# SensorStick_IMUedits_HeaderPins_jesus.net
KiCad netlist of a schematic drawn in EAGLE
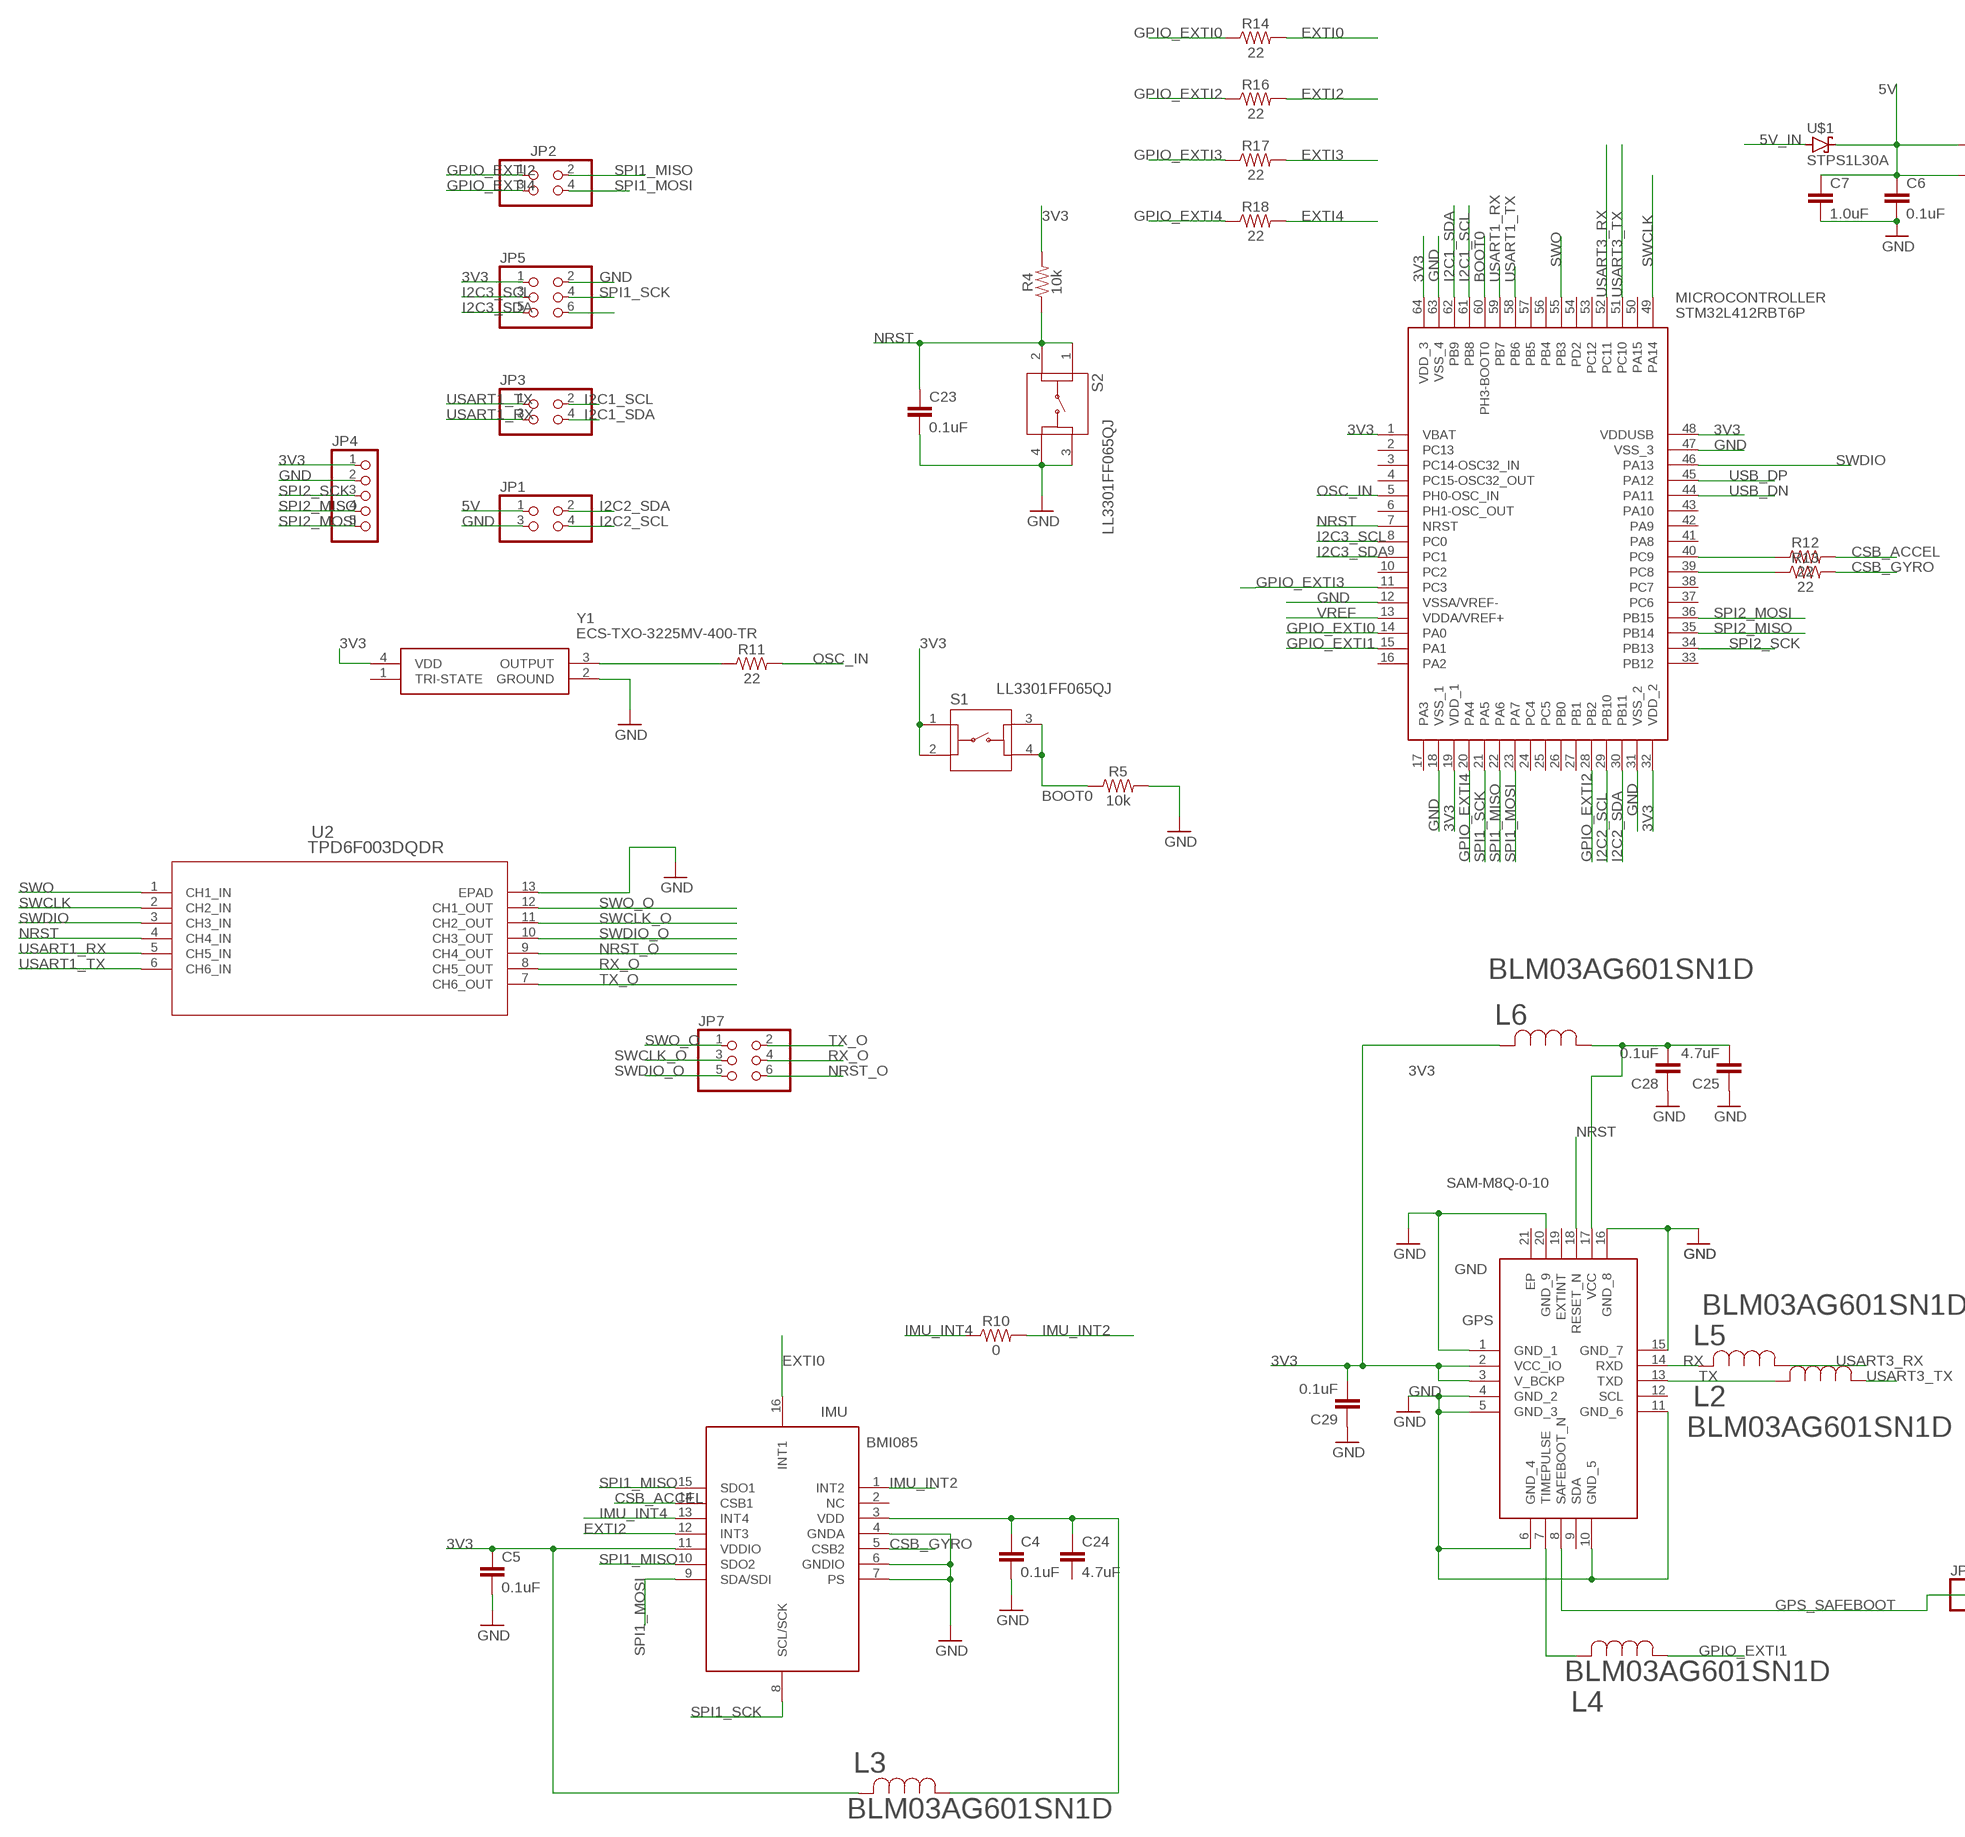
[diagram p0: schematic, sheet 1, part 1 of 2]
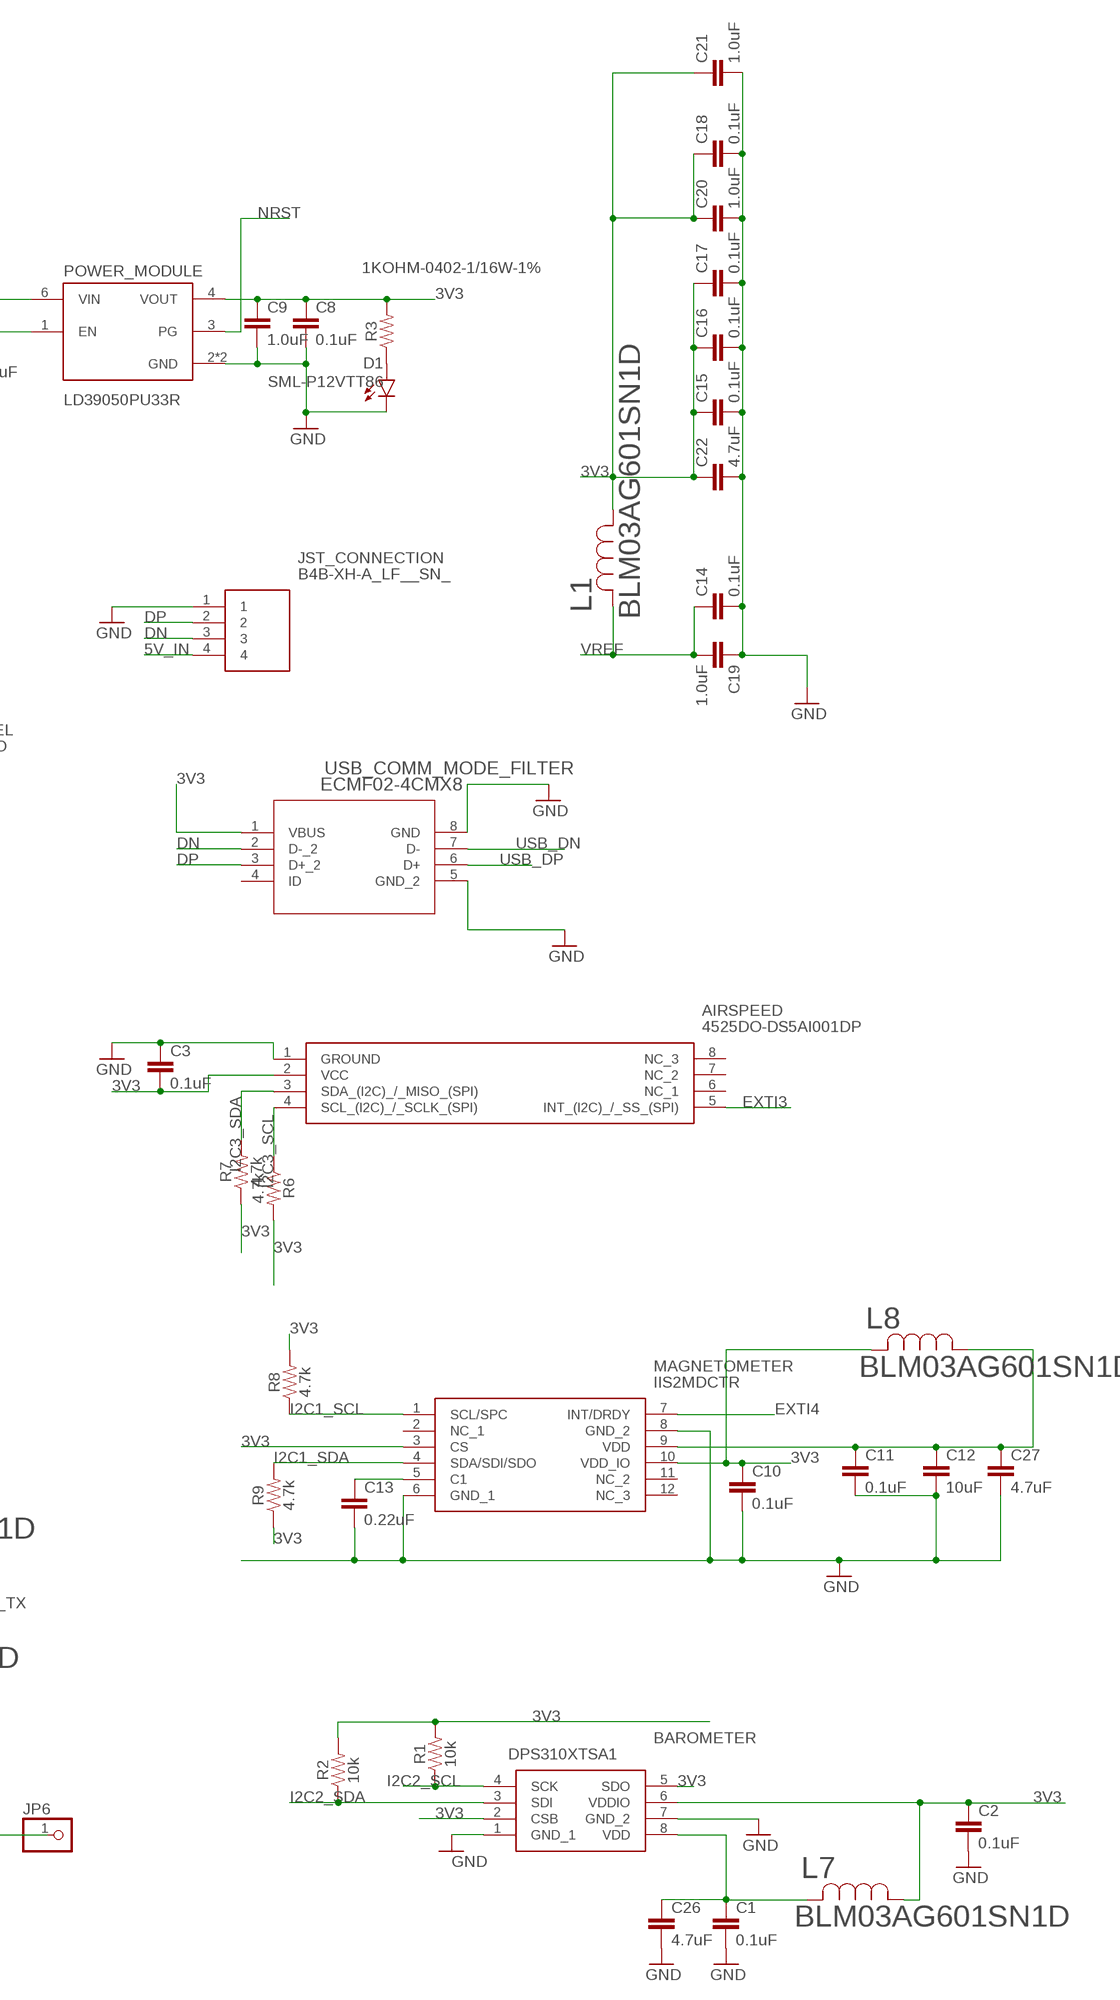
[diagram p1: schematic, sheet 1, part 2 of 2]

(export (version "E")
  (design (tool "Eeschema 10.0.6"))
  (components
    (comp (ref "AIRSPEED")
      (value "4525DO-DS5AI001DP")
      (footprint "eagle-import:4525DO-DS...P")
      (fields (field (name "MOUSER_PART_NUMBER") "824-4525DODS5AI001DP"))
      (libsource (lib "eagle-import") (part "4525DO-DS5AI001DP"))
    )
    (comp (ref "BAROMETER")
      (value "DPS310XTSA1")
      (footprint "eagle-import:DPS310XTSA1")
      (fields (field (name "MOUSER_PART_NUMBER") "726-DPS310XTSA1"))
      (libsource (lib "eagle-import") (part "DPS310XTSA1"))
    )
    (comp (ref "C1")
      (value "0.1uF")
      (footprint "eagle-import:0402")
      (libsource (lib "eagle-import") (part "0.1UF-0402-6.3V-10%-X7R"))
    )
    (comp (ref "C2")
      (value "0.1uF")
      (footprint "eagle-import:0402")
      (libsource (lib "eagle-import") (part "0.1UF-0402-6.3V-10%-X7R"))
    )
    (comp (ref "C3")
      (value "0.1uF")
      (footprint "eagle-import:0402")
      (fields (field (name "SPICEPREFIX") "C"))
      (libsource (lib "eagle-import") (part "0.1UF-0402-6.3V-10%-X7R"))
    )
    (comp (ref "C4")
      (value "0.1uF")
      (footprint "eagle-import:0402")
      (libsource (lib "eagle-import") (part "0.1UF-0402-6.3V-10%-X7R"))
    )
    (comp (ref "C5")
      (value "0.1uF")
      (footprint "eagle-import:0402")
      (libsource (lib "eagle-import") (part "0.1UF-0402-6.3V-10%-X7R"))
    )
    (comp (ref "C6")
      (value "0.1uF")
      (footprint "eagle-import:0402")
      (libsource (lib "eagle-import") (part "0.1UF-0402-6.3V-10%-X7R"))
    )
    (comp (ref "C7")
      (value "1.0uF")
      (footprint "eagle-import:0402")
      (libsource (lib "eagle-import") (part "1.0UF-0402-16V-10%"))
    )
    (comp (ref "C8")
      (value "0.1uF")
      (footprint "eagle-import:0402")
      (libsource (lib "eagle-import") (part "0.1UF-0402-6.3V-10%-X7R"))
    )
    (comp (ref "C9")
      (value "1.0uF")
      (footprint "eagle-import:0402")
      (libsource (lib "eagle-import") (part "1.0UF-0402-16V-10%"))
    )
    (comp (ref "C10")
      (value "0.1uF")
      (footprint "eagle-import:0402")
      (libsource (lib "eagle-import") (part "0.1UF-0402-6.3V-10%-X7R"))
    )
    (comp (ref "C11")
      (value "0.1uF")
      (footprint "eagle-import:0402")
      (libsource (lib "eagle-import") (part "0.1UF-0402-6.3V-10%-X7R"))
    )
    (comp (ref "C12")
      (value "10uF")
      (footprint "eagle-import:0603")
      (libsource (lib "eagle-import") (part "10UF-0603-6.3V-20%"))
    )
    (comp (ref "C13")
      (value "0.22uF")
      (footprint "eagle-import:0603")
      (libsource (lib "eagle-import") (part "0.22UF-0603-25V-10%"))
    )
    (comp (ref "C14")
      (value "0.1uF")
      (footprint "eagle-import:0603")
      (libsource (lib "eagle-import") (part "SparkFun-Capacitors_510_0.1UF-0603-25V-5%"))
    )
    (comp (ref "C15")
      (value "0.1uF")
      (footprint "eagle-import:0603")
      (libsource (lib "eagle-import") (part "SparkFun-Capacitors_510_0.1UF-0603-25V-5%"))
    )
    (comp (ref "C16")
      (value "0.1uF")
      (footprint "eagle-import:0603")
      (libsource (lib "eagle-import") (part "SparkFun-Capacitors_510_0.1UF-0603-25V-5%"))
    )
    (comp (ref "C17")
      (value "0.1uF")
      (footprint "eagle-import:0603")
      (libsource (lib "eagle-import") (part "SparkFun-Capacitors_510_0.1UF-0603-25V-5%"))
    )
    (comp (ref "C18")
      (value "0.1uF")
      (footprint "eagle-import:0603")
      (libsource (lib "eagle-import") (part "SparkFun-Capacitors_510_0.1UF-0603-25V-5%"))
    )
    (comp (ref "C19")
      (value "1.0uF")
      (footprint "eagle-import:0805")
      (libsource (lib "eagle-import") (part "SparkFun-Capacitors_510_1.0UF-0805-25V-10%"))
    )
    (comp (ref "C20")
      (value "1.0uF")
      (footprint "eagle-import:0805")
      (libsource (lib "eagle-import") (part "SparkFun-Capacitors_510_1.0UF-0805-25V-10%"))
    )
    (comp (ref "C21")
      (value "1.0uF")
      (footprint "eagle-import:0805")
      (libsource (lib "eagle-import") (part "SparkFun-Capacitors_510_1.0UF-0805-25V-10%"))
    )
    (comp (ref "C22")
      (value "4.7uF")
      (footprint "eagle-import:0603")
      (libsource (lib "eagle-import") (part "4.7UF0603"))
    )
    (comp (ref "C23")
      (value "0.1uF")
      (footprint "eagle-import:0603")
      (libsource (lib "eagle-import") (part "SparkFun-Capacitors_510_0.1UF-0603-25V-5%"))
    )
    (comp (ref "C24")
      (value "4.7uF")
      (footprint "eagle-import:0603")
      (libsource (lib "eagle-import") (part "4.7UF0603"))
    )
    (comp (ref "C25")
      (value "4.7uF")
      (footprint "eagle-import:0603")
      (libsource (lib "eagle-import") (part "4.7UF0603"))
    )
    (comp (ref "C26")
      (value "4.7uF")
      (footprint "eagle-import:0603")
      (libsource (lib "eagle-import") (part "4.7UF0603"))
    )
    (comp (ref "C27")
      (value "4.7uF")
      (footprint "eagle-import:0603")
      (libsource (lib "eagle-import") (part "4.7UF0603"))
    )
    (comp (ref "C28")
      (value "0.1uF")
      (footprint "eagle-import:0402")
      (libsource (lib "eagle-import") (part "SparkFun-Capacitors_510_0.1UF-0402-16V-10%"))
    )
    (comp (ref "C29")
      (value "0.1uF")
      (footprint "eagle-import:0402")
      (libsource (lib "eagle-import") (part "SparkFun-Capacitors_510_0.1UF-0402-16V-10%"))
    )
    (comp (ref "D1")
      (value "SML-P12VTT86")
      (footprint "eagle-import:LED_SML-P11UTT86R")
      (fields (field (name "MF") "Rohm"))
      (libsource (lib "eagle-import") (part "SML-P12VTT86"))
    )
    (comp (ref "GPS")
      (value "SAM-M8Q-0-10")
      (footprint "eagle-import:SAMM8Q010")
      (libsource (lib "eagle-import") (part "SAM-M8Q-0-10"))
    )
    (comp (ref "IMU")
      (value "BMI085")
      (footprint "eagle-import:BMI085")
      (fields (field (name "MOUSER_PART_NUMBER") "262-BMI085"))
      (libsource (lib "eagle-import") (part "BMI085"))
    )
    (comp (ref "JP1")
      (value "PINHD-2X2")
      (footprint "eagle-import:2X02")
      (libsource (lib "eagle-import") (part "PINHD-2X2"))
    )
    (comp (ref "JP2")
      (value "PINHD-2X2")
      (footprint "eagle-import:2X02")
      (libsource (lib "eagle-import") (part "PINHD-2X2"))
    )
    (comp (ref "JP3")
      (value "PINHD-2X2")
      (footprint "eagle-import:2X02")
      (libsource (lib "eagle-import") (part "PINHD-2X2"))
    )
    (comp (ref "JP4")
      (value "PINHD-1X5")
      (footprint "eagle-import:1X05")
      (libsource (lib "eagle-import") (part "PINHD-1X5"))
    )
    (comp (ref "JP5")
      (value "PINHD-2X3")
      (footprint "eagle-import:2X03")
      (libsource (lib "eagle-import") (part "PINHD-2X3"))
    )
    (comp (ref "JP6")
      (value "PINHD-1X1")
      (footprint "eagle-import:1X01")
      (libsource (lib "eagle-import") (part "PINHD-1X1"))
    )
    (comp (ref "JP7")
      (value "PINHD-2X3")
      (footprint "eagle-import:2X03")
      (libsource (lib "eagle-import") (part "PINHD-2X3"))
    )
    (comp (ref "JST_CONNECTION")
      (value "B4B-XH-A_LF__SN_")
      (footprint "eagle-import:B4BXHALFSN")
      (fields (field (name "ARROW_PART_NUMBER") "B4B-XH-A(LF)(SN)"))
      (libsource (lib "eagle-import") (part "B4B-XH-A_LF__SN_"))
    )
    (comp (ref "L1")
      (value "BLM03AG601SN1D")
      (footprint "eagle-import:IND_BLM03_0201_MUR")
      (fields (field (name "COPYRIGHT") "Copyright (C) 2023 Ultra Librarian. All rights reserved."))
      (libsource (lib "eagle-import") (part "BLM03AG601SN1D"))
    )
    (comp (ref "L2")
      (value "BLM03AG601SN1D")
      (footprint "eagle-import:IND_BLM03_0201_MUR")
      (fields (field (name "COPYRIGHT") "Copyright (C) 2023 Ultra Librarian. All rights reserved."))
      (libsource (lib "eagle-import") (part "BLM03AG601SN1D"))
    )
    (comp (ref "L3")
      (value "BLM03AG601SN1D")
      (footprint "eagle-import:IND_BLM03_0201_MUR")
      (fields (field (name "COPYRIGHT") "Copyright (C) 2023 Ultra Librarian. All rights reserved."))
      (libsource (lib "eagle-import") (part "BLM03AG601SN1D"))
    )
    (comp (ref "L4")
      (value "BLM03AG601SN1D")
      (footprint "eagle-import:IND_BLM03_0201_MUR")
      (fields (field (name "COPYRIGHT") "Copyright (C) 2023 Ultra Librarian. All rights reserved."))
      (libsource (lib "eagle-import") (part "BLM03AG601SN1D"))
    )
    (comp (ref "L5")
      (value "BLM03AG601SN1D")
      (footprint "eagle-import:IND_BLM03_0201_MUR")
      (fields (field (name "COPYRIGHT") "Copyright (C) 2023 Ultra Librarian. All rights reserved."))
      (libsource (lib "eagle-import") (part "BLM03AG601SN1D"))
    )
    (comp (ref "L6")
      (value "BLM03AG601SN1D")
      (footprint "eagle-import:IND_BLM03_0201_MUR")
      (fields (field (name "COPYRIGHT") "Copyright (C) 2023 Ultra Librarian. All rights reserved."))
      (libsource (lib "eagle-import") (part "BLM03AG601SN1D"))
    )
    (comp (ref "L7")
      (value "BLM03AG601SN1D")
      (footprint "eagle-import:IND_BLM03_0201_MUR")
      (fields (field (name "COPYRIGHT") "Copyright (C) 2023 Ultra Librarian. All rights reserved."))
      (libsource (lib "eagle-import") (part "BLM03AG601SN1D"))
    )
    (comp (ref "L8")
      (value "BLM03AG601SN1D")
      (footprint "eagle-import:IND_BLM03_0201_MUR")
      (fields (field (name "COPYRIGHT") "Copyright (C) 2023 Ultra Librarian. All rights reserved."))
      (libsource (lib "eagle-import") (part "BLM03AG601SN1D"))
    )
    (comp (ref "MAGNETOMETER")
      (value "IIS2MDCTR")
      (footprint "eagle-import:IIS2MDCTR")
      (fields (field (name "MOUSER_PART_NUMBER") "511-IIS2MDCTR"))
      (libsource (lib "eagle-import") (part "IIS2MDCTR"))
    )
    (comp (ref "MICROCONTROLLER")
      (value "STM32L412RBT6P")
      (footprint "eagle-import:QFP50P1200X1200X160-64N")
      (fields (field (name "MOUSER_PART_NUMBER") "511-STM32L412RBT6P"))
      (libsource (lib "eagle-import") (part "STM32L412RBT6P"))
    )
    (comp (ref "POWER_MODULE")
      (value "LD39050PU33R")
      (footprint "eagle-import:SON95P300X300X100-7N")
      (fields (field (name "MF") "STMicroelectronics"))
      (libsource (lib "eagle-import") (part "LD39050PU33R"))
    )
    (comp (ref "R1")
      (value "10k")
      (footprint "eagle-import:0402")
      (libsource (lib "eagle-import") (part "10KOHM-0402-1/16W-1%"))
    )
    (comp (ref "R2")
      (value "10k")
      (footprint "eagle-import:0402")
      (libsource (lib "eagle-import") (part "10KOHM-0402-1/16W-1%"))
    )
    (comp (ref "R3")
      (value "1KOHM-0402-1/16W-1%")
      (footprint "eagle-import:0402")
      (libsource (lib "eagle-import") (part "1KOHM-0402-1/16W-1%"))
    )
    (comp (ref "R4")
      (value "10k")
      (footprint "eagle-import:0603")
      (libsource (lib "eagle-import") (part "SparkFun-Resistors_532_10KOHM-0603-1/10W-1%"))
    )
    (comp (ref "R5")
      (value "10k")
      (footprint "eagle-import:0603")
      (libsource (lib "eagle-import") (part "SparkFun-Resistors_532_10KOHM-0603-1/10W-1%"))
    )
    (comp (ref "R6")
      (value "4.7k")
      (footprint "eagle-import:0603")
      (libsource (lib "eagle-import") (part "4.7KOHM-0603-1/10W-1%"))
    )
    (comp (ref "R7")
      (value "4.7k")
      (footprint "eagle-import:0603")
      (libsource (lib "eagle-import") (part "4.7KOHM-0603-1/10W-1%"))
    )
    (comp (ref "R8")
      (value "4.7k")
      (footprint "eagle-import:0603")
      (libsource (lib "eagle-import") (part "4.7KOHM-0603-1/10W-1%"))
    )
    (comp (ref "R9")
      (value "4.7k")
      (footprint "eagle-import:0603")
      (libsource (lib "eagle-import") (part "4.7KOHM-0603-1/10W-1%"))
    )
    (comp (ref "R10")
      (value "0")
      (footprint "eagle-import:0603")
      (libsource (lib "eagle-import") (part "0OHM-0603-1/10W-5%"))
    )
    (comp (ref "R11")
      (value "22")
      (footprint "eagle-import:0402")
      (libsource (lib "eagle-import") (part "22OHM-0402-1/10W-1%"))
    )
    (comp (ref "R12")
      (value "22")
      (footprint "eagle-import:0402")
      (libsource (lib "eagle-import") (part "22OHM-0402-1/10W-1%"))
    )
    (comp (ref "R13")
      (value "22")
      (footprint "eagle-import:0402")
      (libsource (lib "eagle-import") (part "22OHM-0402-1/10W-1%"))
    )
    (comp (ref "R14")
      (value "22")
      (footprint "eagle-import:0402")
      (libsource (lib "eagle-import") (part "22OHM-0402-1/10W-1%"))
    )
    (comp (ref "R16")
      (value "22")
      (footprint "eagle-import:0402")
      (libsource (lib "eagle-import") (part "22OHM-0402-1/10W-1%"))
    )
    (comp (ref "R17")
      (value "22")
      (footprint "eagle-import:0402")
      (libsource (lib "eagle-import") (part "22OHM-0402-1/10W-1%"))
    )
    (comp (ref "R18")
      (value "22")
      (footprint "eagle-import:0402")
      (libsource (lib "eagle-import") (part "22OHM-0402-1/10W-1%"))
    )
    (comp (ref "S1")
      (value "LL3301FF065QJ")
      (footprint "eagle-import:LL3301FF065QJ")
      (fields (field (name "MOUSER_PART_NUMBER") "612-LL3301FF065QJ"))
      (libsource (lib "eagle-import") (part "LL3301FF065QJ"))
    )
    (comp (ref "S2")
      (value "LL3301FF065QJ")
      (footprint "eagle-import:LL3301FF065QJ")
      (fields (field (name "MOUSER_PART_NUMBER") "612-LL3301FF065QJ"))
      (libsource (lib "eagle-import") (part "LL3301FF065QJ"))
    )
    (comp (ref "U$1")
      (value "STPS1L30A")
      (footprint "eagle-import:DIOM5226X223N")
      (libsource (lib "eagle-import") (part "STPS1L30A"))
    )
    (comp (ref "U2")
      (value "TPD6F003DQDR")
      (footprint "eagle-import:DQD12_2X0P4")
      (fields (field (name "COPYRIGHT") "Copyright (C) 2023 Ultra Librarian. All rights reserved."))
      (libsource (lib "eagle-import") (part "TPD6F003DQDR"))
    )
    (comp (ref "USB_COMM_MODE_FILTER")
      (value "ECMF02-4CMX8")
      (footprint "eagle-import:MICRO_QFN-8L_STM")
      (fields (field (name "COPYRIGHT") "Copyright (C) 2023 Ultra Librarian. All rights reserved."))
      (libsource (lib "eagle-import") (part "ECMF02-4CMX8"))
    )
    (comp (ref "Y1")
      (value "ECS-TXO-3225MV-400-TR")
      (footprint "eagle-import:ECSTXO3225MV400TR")
      (libsource (lib "eagle-import") (part "ECS-TXO-3225MV-400-TR"))
    )
  )
  (nets
    (net (code "1") (name "/3V3") (class "Default")
      (node (ref "AIRSPEED") (pin "2") (pinfunction "VCC_2") (pintype "power_in"))
      (node (ref "BAROMETER") (pin "2") (pinfunction "CSB_2") (pintype "bidirectional"))
      (node (ref "BAROMETER") (pin "5") (pinfunction "SDO_5") (pintype "bidirectional"))
      (node (ref "BAROMETER") (pin "6") (pinfunction "VDDIO_6") (pintype "bidirectional"))
      (node (ref "C10") (pin "1") (pinfunction "1_1") (pintype "passive"))
      (node (ref "C15") (pin "1") (pinfunction "1_1") (pintype "passive"))
      (node (ref "C16") (pin "1") (pinfunction "1_1") (pintype "passive"))
      (node (ref "C17") (pin "1") (pinfunction "1_1") (pintype "passive"))
      (node (ref "C18") (pin "1") (pinfunction "1_1") (pintype "passive"))
      (node (ref "C2") (pin "1") (pinfunction "1_1") (pintype "passive"))
      (node (ref "C20") (pin "1") (pinfunction "1_1") (pintype "passive"))
      (node (ref "C21") (pin "1") (pinfunction "1_1") (pintype "passive"))
      (node (ref "C22") (pin "1") (pinfunction "1_1") (pintype "passive"))
      (node (ref "C29") (pin "2") (pinfunction "2_2") (pintype "passive"))
      (node (ref "C3") (pin "2") (pinfunction "2_2") (pintype "passive"))
      (node (ref "C5") (pin "1") (pinfunction "1_1") (pintype "passive"))
      (node (ref "C8") (pin "1") (pinfunction "1_1") (pintype "passive"))
      (node (ref "C9") (pin "1") (pinfunction "1_1") (pintype "passive"))
      (node (ref "GPS") (pin "2") (pinfunction "VCC_IO_2") (pintype "bidirectional"))
      (node (ref "GPS") (pin "3") (pinfunction "V_BCKP_3") (pintype "bidirectional"))
      (node (ref "IMU") (pin "11") (pinfunction "VDDIO_11") (pintype "bidirectional"))
      (node (ref "JP4") (pin "1") (pinfunction "1_1") (pintype "passive"))
      (node (ref "JP5") (pin "1") (pinfunction "1_1") (pintype "passive"))
      (node (ref "L1") (pin "1") (pinfunction "1_1") (pintype "passive"))
      (node (ref "L3") (pin "2") (pinfunction "2_2") (pintype "passive"))
      (node (ref "L6") (pin "2") (pinfunction "2_2") (pintype "passive"))
      (node (ref "L7") (pin "1") (pinfunction "1_1") (pintype "passive"))
      (node (ref "L8") (pin "2") (pinfunction "2_2") (pintype "passive"))
      (node (ref "MAGNETOMETER") (pin "10") (pinfunction "VDD_IO_10") (pintype "bidirectional"))
      (node (ref "MAGNETOMETER") (pin "3") (pinfunction "CS_3") (pintype "bidirectional"))
      (node (ref "MICROCONTROLLER") (pin "1") (pinfunction "VBAT_1") (pintype "bidirectional"))
      (node (ref "MICROCONTROLLER") (pin "19") (pinfunction "VDD_1_19") (pintype "bidirectional"))
      (node (ref "MICROCONTROLLER") (pin "32") (pinfunction "VDD_2_32") (pintype "bidirectional"))
      (node (ref "MICROCONTROLLER") (pin "48") (pinfunction "VDDUSB_48") (pintype "bidirectional"))
      (node (ref "MICROCONTROLLER") (pin "64") (pinfunction "VDD_3_64") (pintype "bidirectional"))
      (node (ref "POWER_MODULE") (pin "4") (pinfunction "VOUT_4") (pintype "output"))
      (node (ref "R1") (pin "2") (pinfunction "2_2") (pintype "passive"))
      (node (ref "R2") (pin "2") (pinfunction "2_2") (pintype "passive"))
      (node (ref "R3") (pin "2") (pinfunction "2_2") (pintype "passive"))
      (node (ref "R4") (pin "2") (pinfunction "2_2") (pintype "passive"))
      (node (ref "R6") (pin "2") (pinfunction "2_2") (pintype "passive"))
      (node (ref "R7") (pin "1") (pinfunction "1_1") (pintype "passive"))
      (node (ref "R8") (pin "2") (pinfunction "2_2") (pintype "passive"))
      (node (ref "R9") (pin "1") (pinfunction "1_1") (pintype "passive"))
      (node (ref "S1") (pin "1") (pinfunction "1_1") (pintype "passive"))
      (node (ref "S1") (pin "2") (pinfunction "2_2") (pintype "passive"))
      (node (ref "USB_COMM_MODE_FILTER") (pin "1") (pinfunction "VBUS_1") (pintype "power_in"))
      (node (ref "Y1") (pin "4") (pinfunction "VDD_4") (pintype "bidirectional"))
    )
    (net (code "2") (name "/5V") (class "Default")
      (node (ref "C6") (pin "1") (pinfunction "1_1") (pintype "passive"))
      (node (ref "C7") (pin "1") (pinfunction "1_1") (pintype "passive"))
      (node (ref "JP1") (pin "1") (pinfunction "1_1") (pintype "passive"))
      (node (ref "POWER_MODULE") (pin "1") (pinfunction "EN_1") (pintype "input"))
      (node (ref "POWER_MODULE") (pin "6") (pinfunction "VIN_6") (pintype "power_in"))
      (node (ref "U$1") (pin "1") (pinfunction "C_1") (pintype "passive"))
    )
    (net (code "3") (name "/5V_IN") (class "Default")
      (node (ref "JST_CONNECTION") (pin "4") (pinfunction "4_4") (pintype "bidirectional"))
      (node (ref "U$1") (pin "2") (pinfunction "A_2") (pintype "passive"))
    )
    (net (code "4") (name "/BOOT0") (class "Default")
      (node (ref "MICROCONTROLLER") (pin "60") (pinfunction "PH3-BOOT0_60") (pintype "bidirectional"))
      (node (ref "R5") (pin "1") (pinfunction "1_1") (pintype "passive"))
      (node (ref "S1") (pin "3") (pinfunction "3_3") (pintype "passive"))
      (node (ref "S1") (pin "4") (pinfunction "4_4") (pintype "passive"))
    )
    (net (code "5") (name "/CSB_ACCEL") (class "Default")
      (node (ref "IMU") (pin "14") (pinfunction "CSB1_14") (pintype "bidirectional"))
      (node (ref "R12") (pin "2") (pinfunction "2_2") (pintype "passive"))
    )
    (net (code "6") (name "/CSB_GYRO") (class "Default")
      (node (ref "IMU") (pin "5") (pinfunction "CSB2_5") (pintype "bidirectional"))
      (node (ref "R13") (pin "2") (pinfunction "2_2") (pintype "passive"))
    )
    (net (code "7") (name "/DN") (class "Default")
      (node (ref "JST_CONNECTION") (pin "3") (pinfunction "3_3") (pintype "bidirectional"))
      (node (ref "USB_COMM_MODE_FILTER") (pin "2") (pinfunction "D-_2_2") (pintype "bidirectional"))
    )
    (net (code "8") (name "/DP") (class "Default")
      (node (ref "JST_CONNECTION") (pin "2") (pinfunction "2_2") (pintype "bidirectional"))
      (node (ref "USB_COMM_MODE_FILTER") (pin "3") (pinfunction "D+_2_3") (pintype "bidirectional"))
    )
    (net (code "9") (name "/EXTI0") (class "Default")
      (node (ref "IMU") (pin "16") (pinfunction "INT1_16") (pintype "bidirectional"))
      (node (ref "R14") (pin "2") (pinfunction "2_2") (pintype "passive"))
    )
    (net (code "10") (name "/EXTI2") (class "Default")
      (node (ref "IMU") (pin "12") (pinfunction "INT3_12") (pintype "bidirectional"))
      (node (ref "R16") (pin "2") (pinfunction "2_2") (pintype "passive"))
    )
    (net (code "11") (name "/EXTI3") (class "Default")
      (node (ref "AIRSPEED") (pin "5") (pinfunction "INT_(I2C)_/_SS_(SPI)_5") (pintype "bidirectional"))
      (node (ref "R17") (pin "2") (pinfunction "2_2") (pintype "passive"))
    )
    (net (code "12") (name "/EXTI4") (class "Default")
      (node (ref "MAGNETOMETER") (pin "7") (pinfunction "INT/DRDY_7") (pintype "bidirectional"))
      (node (ref "R18") (pin "2") (pinfunction "2_2") (pintype "passive"))
    )
    (net (code "13") (name "/GPIO_EXTI0") (class "Default")
      (node (ref "MICROCONTROLLER") (pin "14") (pinfunction "PA0_14") (pintype "bidirectional"))
      (node (ref "R14") (pin "1") (pinfunction "1_1") (pintype "passive"))
    )
    (net (code "14") (name "/GPIO_EXTI1") (class "Default")
      (node (ref "L4") (pin "1") (pinfunction "1_1") (pintype "passive"))
      (node (ref "MICROCONTROLLER") (pin "15") (pinfunction "PA1_15") (pintype "bidirectional"))
    )
    (net (code "15") (name "/GPIO_EXTI2") (class "Default")
      (node (ref "JP2") (pin "1") (pinfunction "1_1") (pintype "passive"))
      (node (ref "MICROCONTROLLER") (pin "28") (pinfunction "PB2_28") (pintype "bidirectional"))
      (node (ref "R16") (pin "1") (pinfunction "1_1") (pintype "passive"))
    )
    (net (code "16") (name "/GPIO_EXTI3") (class "Default")
      (node (ref "MICROCONTROLLER") (pin "11") (pinfunction "PC3_11") (pintype "bidirectional"))
      (node (ref "R17") (pin "1") (pinfunction "1_1") (pintype "passive"))
    )
    (net (code "17") (name "/GPIO_EXTI4") (class "Default")
      (node (ref "JP2") (pin "3") (pinfunction "3_3") (pintype "passive"))
      (node (ref "MICROCONTROLLER") (pin "20") (pinfunction "PA4_20") (pintype "bidirectional"))
      (node (ref "R18") (pin "1") (pinfunction "1_1") (pintype "passive"))
    )
    (net (code "18") (name "/GPS_SAFEBOOT") (class "Default")
      (node (ref "GPS") (pin "8") (pinfunction "SAFEBOOT_N_8") (pintype "bidirectional"))
      (node (ref "JP6") (pin "1") (pinfunction "1_1") (pintype "passive"))
    )
    (net (code "19") (name "/I2C1_SCL") (class "Default")
      (node (ref "JP3") (pin "2") (pinfunction "2_2") (pintype "passive"))
      (node (ref "MAGNETOMETER") (pin "1") (pinfunction "SCL/SPC_1") (pintype "bidirectional"))
      (node (ref "MICROCONTROLLER") (pin "61") (pinfunction "PB8_61") (pintype "bidirectional"))
      (node (ref "R8") (pin "1") (pinfunction "1_1") (pintype "passive"))
    )
    (net (code "20") (name "/I2C1_SDA") (class "Default")
      (node (ref "JP3") (pin "4") (pinfunction "4_4") (pintype "passive"))
      (node (ref "MAGNETOMETER") (pin "4") (pinfunction "SDA/SDI/SDO_4") (pintype "bidirectional"))
      (node (ref "MICROCONTROLLER") (pin "62") (pinfunction "PB9_62") (pintype "bidirectional"))
      (node (ref "R9") (pin "2") (pinfunction "2_2") (pintype "passive"))
    )
    (net (code "21") (name "/I2C2_SCL") (class "Default")
      (node (ref "BAROMETER") (pin "4") (pinfunction "SCK_4") (pintype "bidirectional"))
      (node (ref "JP1") (pin "4") (pinfunction "4_4") (pintype "passive"))
      (node (ref "MICROCONTROLLER") (pin "29") (pinfunction "PB10_29") (pintype "bidirectional"))
      (node (ref "R1") (pin "1") (pinfunction "1_1") (pintype "passive"))
    )
    (net (code "22") (name "/I2C2_SDA") (class "Default")
      (node (ref "BAROMETER") (pin "3") (pinfunction "SDI_3") (pintype "bidirectional"))
      (node (ref "JP1") (pin "2") (pinfunction "2_2") (pintype "passive"))
      (node (ref "MICROCONTROLLER") (pin "30") (pinfunction "PB11_30") (pintype "bidirectional"))
      (node (ref "R2") (pin "1") (pinfunction "1_1") (pintype "passive"))
    )
    (net (code "23") (name "/I2C3_SCL") (class "Default")
      (node (ref "AIRSPEED") (pin "4") (pinfunction "SCL_(I2C)_/_SCLK_(SPI)_4") (pintype "bidirectional"))
      (node (ref "JP5") (pin "3") (pinfunction "3_3") (pintype "passive"))
      (node (ref "MICROCONTROLLER") (pin "8") (pinfunction "PC0_8") (pintype "bidirectional"))
      (node (ref "R6") (pin "1") (pinfunction "1_1") (pintype "passive"))
    )
    (net (code "24") (name "/I2C3_SDA") (class "Default")
      (node (ref "AIRSPEED") (pin "3") (pinfunction "SDA_(I2C)_/_MISO_(SPI)_3") (pintype "bidirectional"))
      (node (ref "JP5") (pin "5") (pinfunction "5_5") (pintype "passive"))
      (node (ref "MICROCONTROLLER") (pin "9") (pinfunction "PC1_9") (pintype "bidirectional"))
      (node (ref "R7") (pin "2") (pinfunction "2_2") (pintype "passive"))
    )
    (net (code "25") (name "/IMU_INT2") (class "Default")
      (node (ref "IMU") (pin "1") (pinfunction "INT2_1") (pintype "bidirectional"))
      (node (ref "R10") (pin "2") (pinfunction "2_2") (pintype "passive"))
    )
    (net (code "26") (name "/IMU_INT4") (class "Default")
      (node (ref "IMU") (pin "13") (pinfunction "INT4_13") (pintype "bidirectional"))
      (node (ref "R10") (pin "1") (pinfunction "1_1") (pintype "passive"))
    )
    (net (code "27") (name "/NRST") (class "Default")
      (node (ref "C23") (pin "1") (pinfunction "1_1") (pintype "passive"))
      (node (ref "GPS") (pin "18") (pinfunction "RESET_N_18") (pintype "bidirectional"))
      (node (ref "MICROCONTROLLER") (pin "7") (pinfunction "NRST_7") (pintype "bidirectional"))
      (node (ref "POWER_MODULE") (pin "3") (pinfunction "PG_3") (pintype "bidirectional"))
      (node (ref "R4") (pin "1") (pinfunction "1_1") (pintype "passive"))
      (node (ref "S2") (pin "1") (pinfunction "1_1") (pintype "passive"))
      (node (ref "S2") (pin "2") (pinfunction "2_2") (pintype "passive"))
      (node (ref "U2") (pin "4") (pinfunction "CH4_IN_4") (pintype "input"))
    )
    (net (code "28") (name "/NRST_O") (class "Default")
      (node (ref "JP7") (pin "6") (pinfunction "6_6") (pintype "passive"))
      (node (ref "U2") (pin "9") (pinfunction "CH4_OUT_9") (pintype "output"))
    )
    (net (code "29") (name "/OSC_IN") (class "Default")
      (node (ref "MICROCONTROLLER") (pin "5") (pinfunction "PH0-OSC_IN_5") (pintype "bidirectional"))
      (node (ref "R11") (pin "2") (pinfunction "2_2") (pintype "passive"))
    )
    (net (code "30") (name "/RX") (class "Default")
      (node (ref "GPS") (pin "14") (pinfunction "RXD_14") (pintype "bidirectional"))
      (node (ref "L5") (pin "2") (pinfunction "2_2") (pintype "passive"))
    )
    (net (code "31") (name "/RX_O") (class "Default")
      (node (ref "JP7") (pin "4") (pinfunction "4_4") (pintype "passive"))
      (node (ref "U2") (pin "8") (pinfunction "CH5_OUT_8") (pintype "output"))
    )
    (net (code "32") (name "/SPI1_MISO") (class "Default")
      (node (ref "IMU") (pin "10") (pinfunction "SDO2_10") (pintype "bidirectional"))
      (node (ref "IMU") (pin "15") (pinfunction "SDO1_15") (pintype "bidirectional"))
      (node (ref "JP2") (pin "2") (pinfunction "2_2") (pintype "passive"))
      (node (ref "MICROCONTROLLER") (pin "22") (pinfunction "PA6_22") (pintype "bidirectional"))
    )
    (net (code "33") (name "/SPI1_MOSI") (class "Default")
      (node (ref "IMU") (pin "9") (pinfunction "SDA/SDI_9") (pintype "bidirectional"))
      (node (ref "JP2") (pin "4") (pinfunction "4_4") (pintype "passive"))
      (node (ref "MICROCONTROLLER") (pin "23") (pinfunction "PA7_23") (pintype "bidirectional"))
    )
    (net (code "34") (name "/SPI1_SCK") (class "Default")
      (node (ref "IMU") (pin "8") (pinfunction "SCL/SCK_8") (pintype "bidirectional"))
      (node (ref "JP5") (pin "4") (pinfunction "4_4") (pintype "passive"))
      (node (ref "MICROCONTROLLER") (pin "21") (pinfunction "PA5_21") (pintype "bidirectional"))
    )
    (net (code "35") (name "/SPI2_MISO") (class "Default")
      (node (ref "JP4") (pin "4") (pinfunction "4_4") (pintype "passive"))
      (node (ref "MICROCONTROLLER") (pin "35") (pinfunction "PB14_35") (pintype "bidirectional"))
    )
    (net (code "36") (name "/SPI2_MOSI") (class "Default")
      (node (ref "JP4") (pin "5") (pinfunction "5_5") (pintype "passive"))
      (node (ref "MICROCONTROLLER") (pin "36") (pinfunction "PB15_36") (pintype "bidirectional"))
    )
    (net (code "37") (name "/SPI2_SCK") (class "Default")
      (node (ref "JP4") (pin "3") (pinfunction "3_3") (pintype "passive"))
      (node (ref "MICROCONTROLLER") (pin "34") (pinfunction "PB13_34") (pintype "bidirectional"))
    )
    (net (code "38") (name "/SWCLK") (class "Default")
      (node (ref "MICROCONTROLLER") (pin "49") (pinfunction "PA14_49") (pintype "bidirectional"))
      (node (ref "U2") (pin "2") (pinfunction "CH2_IN_2") (pintype "input"))
    )
    (net (code "39") (name "/SWCLK_O") (class "Default")
      (node (ref "JP7") (pin "3") (pinfunction "3_3") (pintype "passive"))
      (node (ref "U2") (pin "11") (pinfunction "CH2_OUT_11") (pintype "output"))
    )
    (net (code "40") (name "/SWDIO") (class "Default")
      (node (ref "MICROCONTROLLER") (pin "46") (pinfunction "PA13_46") (pintype "bidirectional"))
      (node (ref "U2") (pin "3") (pinfunction "CH3_IN_3") (pintype "input"))
    )
    (net (code "41") (name "/SWDIO_O") (class "Default")
      (node (ref "JP7") (pin "5") (pinfunction "5_5") (pintype "passive"))
      (node (ref "U2") (pin "10") (pinfunction "CH3_OUT_10") (pintype "output"))
    )
    (net (code "42") (name "/SWO") (class "Default")
      (node (ref "MICROCONTROLLER") (pin "55") (pinfunction "PB3_55") (pintype "bidirectional"))
      (node (ref "U2") (pin "1") (pinfunction "CH1_IN_1") (pintype "input"))
    )
    (net (code "43") (name "/SWO_O") (class "Default")
      (node (ref "JP7") (pin "1") (pinfunction "1_1") (pintype "passive"))
      (node (ref "U2") (pin "12") (pinfunction "CH1_OUT_12") (pintype "output"))
    )
    (net (code "44") (name "/TX") (class "Default")
      (node (ref "GPS") (pin "13") (pinfunction "TXD_13") (pintype "bidirectional"))
      (node (ref "L2") (pin "2") (pinfunction "2_2") (pintype "passive"))
    )
    (net (code "45") (name "/TX_O") (class "Default")
      (node (ref "JP7") (pin "2") (pinfunction "2_2") (pintype "passive"))
      (node (ref "U2") (pin "7") (pinfunction "CH6_OUT_7") (pintype "output"))
    )
    (net (code "46") (name "/USART1_RX") (class "Default")
      (node (ref "JP3") (pin "3") (pinfunction "3_3") (pintype "passive"))
      (node (ref "MICROCONTROLLER") (pin "59") (pinfunction "PB7_59") (pintype "bidirectional"))
      (node (ref "U2") (pin "5") (pinfunction "CH5_IN_5") (pintype "input"))
    )
    (net (code "47") (name "/USART1_TX") (class "Default")
      (node (ref "JP3") (pin "1") (pinfunction "1_1") (pintype "passive"))
      (node (ref "MICROCONTROLLER") (pin "58") (pinfunction "PB6_58") (pintype "bidirectional"))
      (node (ref "U2") (pin "6") (pinfunction "CH6_IN_6") (pintype "input"))
    )
    (net (code "48") (name "/USART3_RX") (class "Default")
      (node (ref "L5") (pin "1") (pinfunction "1_1") (pintype "passive"))
      (node (ref "MICROCONTROLLER") (pin "52") (pinfunction "PC11_52") (pintype "bidirectional"))
    )
    (net (code "49") (name "/USART3_TX") (class "Default")
      (node (ref "L2") (pin "1") (pinfunction "1_1") (pintype "passive"))
      (node (ref "MICROCONTROLLER") (pin "51") (pinfunction "PC10_51") (pintype "bidirectional"))
    )
    (net (code "50") (name "/USB_DN") (class "Default")
      (node (ref "MICROCONTROLLER") (pin "44") (pinfunction "PA11_44") (pintype "bidirectional"))
      (node (ref "USB_COMM_MODE_FILTER") (pin "7") (pinfunction "D-_7") (pintype "bidirectional"))
    )
    (net (code "51") (name "/USB_DP") (class "Default")
      (node (ref "MICROCONTROLLER") (pin "45") (pinfunction "PA12_45") (pintype "bidirectional"))
      (node (ref "USB_COMM_MODE_FILTER") (pin "6") (pinfunction "D+_6") (pintype "bidirectional"))
    )
    (net (code "52") (name "/VREF") (class "Default")
      (node (ref "C14") (pin "1") (pinfunction "1_1") (pintype "passive"))
      (node (ref "C19") (pin "2") (pinfunction "2_2") (pintype "passive"))
      (node (ref "L1") (pin "2") (pinfunction "2_2") (pintype "passive"))
      (node (ref "MICROCONTROLLER") (pin "13") (pinfunction "VDDA/VREF+_13") (pintype "bidirectional"))
    )
    (net (code "53") (name "GND") (class "Default")
      (node (ref "AIRSPEED") (pin "1") (pinfunction "GROUND_1") (pintype "power_in"))
      (node (ref "BAROMETER") (pin "1") (pinfunction "GND_1_1") (pintype "bidirectional"))
      (node (ref "BAROMETER") (pin "7") (pinfunction "GND_2_7") (pintype "bidirectional"))
      (node (ref "C1") (pin "2") (pinfunction "2_2") (pintype "passive"))
      (node (ref "C10") (pin "2") (pinfunction "2_2") (pintype "passive"))
      (node (ref "C11") (pin "2") (pinfunction "2_2") (pintype "passive"))
      (node (ref "C12") (pin "2") (pinfunction "2_2") (pintype "passive"))
      (node (ref "C13") (pin "2") (pinfunction "2_2") (pintype "passive"))
      (node (ref "C14") (pin "2") (pinfunction "2_2") (pintype "passive"))
      (node (ref "C15") (pin "2") (pinfunction "2_2") (pintype "passive"))
      (node (ref "C16") (pin "2") (pinfunction "2_2") (pintype "passive"))
      (node (ref "C17") (pin "2") (pinfunction "2_2") (pintype "passive"))
      (node (ref "C18") (pin "2") (pinfunction "2_2") (pintype "passive"))
      (node (ref "C19") (pin "1") (pinfunction "1_1") (pintype "passive"))
      (node (ref "C2") (pin "2") (pinfunction "2_2") (pintype "passive"))
      (node (ref "C20") (pin "2") (pinfunction "2_2") (pintype "passive"))
      (node (ref "C21") (pin "2") (pinfunction "2_2") (pintype "passive"))
      (node (ref "C22") (pin "2") (pinfunction "2_2") (pintype "passive"))
      (node (ref "C23") (pin "2") (pinfunction "2_2") (pintype "passive"))
      (node (ref "C25") (pin "1") (pinfunction "1_1") (pintype "passive"))
      (node (ref "C26") (pin "2") (pinfunction "2_2") (pintype "passive"))
      (node (ref "C27") (pin "2") (pinfunction "2_2") (pintype "passive"))
      (node (ref "C28") (pin "1") (pinfunction "1_1") (pintype "passive"))
      (node (ref "C29") (pin "1") (pinfunction "1_1") (pintype "passive"))
      (node (ref "C3") (pin "1") (pinfunction "1_1") (pintype "passive"))
      (node (ref "C4") (pin "2") (pinfunction "2_2") (pintype "passive"))
      (node (ref "C5") (pin "2") (pinfunction "2_2") (pintype "passive"))
      (node (ref "C6") (pin "2") (pinfunction "2_2") (pintype "passive"))
      (node (ref "C7") (pin "2") (pinfunction "2_2") (pintype "passive"))
      (node (ref "C8") (pin "2") (pinfunction "2_2") (pintype "passive"))
      (node (ref "C9") (pin "2") (pinfunction "2_2") (pintype "passive"))
      (node (ref "D1") (pin "C") (pinfunction "C_C") (pintype "passive"))
      (node (ref "GPS") (pin "1") (pinfunction "GND_1_1") (pintype "bidirectional"))
      (node (ref "GPS") (pin "10") (pinfunction "GND_5_10") (pintype "bidirectional"))
      (node (ref "GPS") (pin "11") (pinfunction "GND_6_11") (pintype "bidirectional"))
      (node (ref "GPS") (pin "15") (pinfunction "GND_7_15") (pintype "bidirectional"))
      (node (ref "GPS") (pin "16") (pinfunction "GND_8_16") (pintype "bidirectional"))
      (node (ref "GPS") (pin "20") (pinfunction "GND_9_20") (pintype "bidirectional"))
      (node (ref "GPS") (pin "4") (pinfunction "GND_2_4") (pintype "bidirectional"))
      (node (ref "GPS") (pin "5") (pinfunction "GND_3_5") (pintype "bidirectional"))
      (node (ref "GPS") (pin "6") (pinfunction "GND_4_6") (pintype "bidirectional"))
      (node (ref "IMU") (pin "4") (pinfunction "GNDA_4") (pintype "bidirectional"))
      (node (ref "IMU") (pin "6") (pinfunction "GNDIO_6") (pintype "bidirectional"))
      (node (ref "IMU") (pin "7") (pinfunction "PS_7") (pintype "bidirectional"))
      (node (ref "JP1") (pin "3") (pinfunction "3_3") (pintype "passive"))
      (node (ref "JP4") (pin "2") (pinfunction "2_2") (pintype "passive"))
      (node (ref "JP5") (pin "2") (pinfunction "2_2") (pintype "passive"))
      (node (ref "JST_CONNECTION") (pin "1") (pinfunction "1_1") (pintype "bidirectional"))
      (node (ref "MAGNETOMETER") (pin "6") (pinfunction "GND_1_6") (pintype "bidirectional"))
      (node (ref "MAGNETOMETER") (pin "8") (pinfunction "GND_2_8") (pintype "bidirectional"))
      (node (ref "MICROCONTROLLER") (pin "12") (pinfunction "VSSA/VREF-_12") (pintype "bidirectional"))
      (node (ref "MICROCONTROLLER") (pin "18") (pinfunction "VSS_1_18") (pintype "bidirectional"))
      (node (ref "MICROCONTROLLER") (pin "31") (pinfunction "VSS_2_31") (pintype "bidirectional"))
      (node (ref "MICROCONTROLLER") (pin "47") (pinfunction "VSS_3_47") (pintype "bidirectional"))
      (node (ref "MICROCONTROLLER") (pin "63") (pinfunction "VSS_4_63") (pintype "bidirectional"))
      (node (ref "POWER_MODULE") (pin "2") (pinfunction "GND_2") (pintype "power_in"))
      (node (ref "POWER_MODULE") (pin "7") (pinfunction "GND_7") (pintype "power_in"))
      (node (ref "R5") (pin "2") (pinfunction "2_2") (pintype "passive"))
      (node (ref "S2") (pin "3") (pinfunction "3_3") (pintype "passive"))
      (node (ref "S2") (pin "4") (pinfunction "4_4") (pintype "passive"))
      (node (ref "U2") (pin "13") (pinfunction "EPAD_13") (pintype "passive"))
      (node (ref "USB_COMM_MODE_FILTER") (pin "5") (pinfunction "GND_2_5") (pintype "passive"))
      (node (ref "USB_COMM_MODE_FILTER") (pin "8") (pinfunction "GND_8") (pintype "passive"))
      (node (ref "Y1") (pin "2") (pinfunction "GROUND_2") (pintype "bidirectional"))
    )
    (net (code "54") (name "Net-(BAROMETER-VDD)") (class "Default")
      (node (ref "BAROMETER") (pin "8") (pinfunction "VDD_8") (pintype "bidirectional"))
      (node (ref "C1") (pin "1") (pinfunction "1_1") (pintype "passive"))
      (node (ref "C26") (pin "1") (pinfunction "1_1") (pintype "passive"))
      (node (ref "L7") (pin "2") (pinfunction "2_2") (pintype "passive"))
    )
    (net (code "55") (name "Net-(D1-PadA)") (class "Default")
      (node (ref "D1") (pin "A") (pinfunction "A_A") (pintype "passive"))
      (node (ref "R3") (pin "1") (pinfunction "1_1") (pintype "passive"))
    )
    (net (code "56") (name "Net-(GPS-TIMEPULSE)") (class "Default")
      (node (ref "GPS") (pin "7") (pinfunction "TIMEPULSE_7") (pintype "bidirectional"))
      (node (ref "L4") (pin "2") (pinfunction "2_2") (pintype "passive"))
    )
    (net (code "57") (name "Net-(GPS-VCC)") (class "Default")
      (node (ref "C25") (pin "2") (pinfunction "2_2") (pintype "passive"))
      (node (ref "C28") (pin "2") (pinfunction "2_2") (pintype "passive"))
      (node (ref "GPS") (pin "17") (pinfunction "VCC_17") (pintype "bidirectional"))
      (node (ref "L6") (pin "1") (pinfunction "1_1") (pintype "passive"))
    )
    (net (code "58") (name "Net-(IMU-VDD)") (class "Default")
      (node (ref "C24") (pin "1") (pinfunction "1_1") (pintype "passive"))
      (node (ref "C4") (pin "1") (pinfunction "1_1") (pintype "passive"))
      (node (ref "IMU") (pin "3") (pinfunction "VDD_3") (pintype "bidirectional"))
      (node (ref "L3") (pin "1") (pinfunction "1_1") (pintype "passive"))
    )
    (net (code "59") (name "Net-(MAGNETOMETER-C1)") (class "Default")
      (node (ref "C13") (pin "1") (pinfunction "1_1") (pintype "passive"))
      (node (ref "MAGNETOMETER") (pin "5") (pinfunction "C1_5") (pintype "bidirectional"))
    )
    (net (code "60") (name "Net-(MAGNETOMETER-VDD)") (class "Default")
      (node (ref "C11") (pin "1") (pinfunction "1_1") (pintype "passive"))
      (node (ref "C12") (pin "1") (pinfunction "1_1") (pintype "passive"))
      (node (ref "C27") (pin "1") (pinfunction "1_1") (pintype "passive"))
      (node (ref "L8") (pin "1") (pinfunction "1_1") (pintype "passive"))
      (node (ref "MAGNETOMETER") (pin "9") (pinfunction "VDD_9") (pintype "bidirectional"))
    )
    (net (code "61") (name "Net-(MICROCONTROLLER-PC8)") (class "Default")
      (node (ref "MICROCONTROLLER") (pin "39") (pinfunction "PC8_39") (pintype "bidirectional"))
      (node (ref "R13") (pin "1") (pinfunction "1_1") (pintype "passive"))
    )
    (net (code "62") (name "Net-(MICROCONTROLLER-PC9)") (class "Default")
      (node (ref "MICROCONTROLLER") (pin "40") (pinfunction "PC9_40") (pintype "bidirectional"))
      (node (ref "R12") (pin "1") (pinfunction "1_1") (pintype "passive"))
    )
    (net (code "63") (name "Net-(Y1-OUTPUT)") (class "Default")
      (node (ref "R11") (pin "1") (pinfunction "1_1") (pintype "passive"))
      (node (ref "Y1") (pin "3") (pinfunction "OUTPUT_3") (pintype "bidirectional"))
    )
    (net (code "64") (name "unconnected-(AIRSPEED-NC_1-Pad6)") (class "Default")
      (node (ref "AIRSPEED") (pin "6") (pinfunction "NC_1_6") (pintype "bidirectional"))
    )
    (net (code "65") (name "unconnected-(AIRSPEED-NC_2-Pad7)") (class "Default")
      (node (ref "AIRSPEED") (pin "7") (pinfunction "NC_2_7") (pintype "bidirectional"))
    )
    (net (code "66") (name "unconnected-(AIRSPEED-NC_3-Pad8)") (class "Default")
      (node (ref "AIRSPEED") (pin "8") (pinfunction "NC_3_8") (pintype "bidirectional"))
    )
    (net (code "67") (name "unconnected-(C24-Pad2)") (class "Default")
      (node (ref "C24") (pin "2") (pinfunction "2_2") (pintype "passive"))
    )
    (net (code "68") (name "unconnected-(GPS-EP-Pad21)") (class "Default")
      (node (ref "GPS") (pin "21") (pinfunction "EP_21") (pintype "bidirectional"))
    )
    (net (code "69") (name "unconnected-(GPS-EXTINT-Pad19)") (class "Default")
      (node (ref "GPS") (pin "19") (pinfunction "EXTINT_19") (pintype "bidirectional"))
    )
    (net (code "70") (name "unconnected-(GPS-SCL-Pad12)") (class "Default")
      (node (ref "GPS") (pin "12") (pinfunction "SCL_12") (pintype "bidirectional"))
    )
    (net (code "71") (name "unconnected-(GPS-SDA-Pad9)") (class "Default")
      (node (ref "GPS") (pin "9") (pinfunction "SDA_9") (pintype "bidirectional"))
    )
    (net (code "72") (name "unconnected-(IMU-NC-Pad2)") (class "Default")
      (node (ref "IMU") (pin "2") (pinfunction "NC_2") (pintype "no_connect"))
    )
    (net (code "73") (name "unconnected-(JP5-Pad6)") (class "Default")
      (node (ref "JP5") (pin "6") (pinfunction "6_6") (pintype "passive"))
    )
    (net (code "74") (name "unconnected-(MAGNETOMETER-NC_1-Pad2)") (class "Default")
      (node (ref "MAGNETOMETER") (pin "2") (pinfunction "NC_1_2") (pintype "bidirectional"))
    )
    (net (code "75") (name "unconnected-(MAGNETOMETER-NC_2-Pad11)") (class "Default")
      (node (ref "MAGNETOMETER") (pin "11") (pinfunction "NC_2_11") (pintype "bidirectional"))
    )
    (net (code "76") (name "unconnected-(MAGNETOMETER-NC_3-Pad12)") (class "Default")
      (node (ref "MAGNETOMETER") (pin "12") (pinfunction "NC_3_12") (pintype "bidirectional"))
    )
    (net (code "77") (name "unconnected-(MICROCONTROLLER-PA2-Pad16)") (class "Default")
      (node (ref "MICROCONTROLLER") (pin "16") (pinfunction "PA2_16") (pintype "bidirectional"))
    )
    (net (code "78") (name "unconnected-(MICROCONTROLLER-PA3-Pad17)") (class "Default")
      (node (ref "MICROCONTROLLER") (pin "17") (pinfunction "PA3_17") (pintype "bidirectional"))
    )
    (net (code "79") (name "unconnected-(MICROCONTROLLER-PA8-Pad41)") (class "Default")
      (node (ref "MICROCONTROLLER") (pin "41") (pinfunction "PA8_41") (pintype "bidirectional"))
    )
    (net (code "80") (name "unconnected-(MICROCONTROLLER-PA9-Pad42)") (class "Default")
      (node (ref "MICROCONTROLLER") (pin "42") (pinfunction "PA9_42") (pintype "bidirectional"))
    )
    (net (code "81") (name "unconnected-(MICROCONTROLLER-PA10-Pad43)") (class "Default")
      (node (ref "MICROCONTROLLER") (pin "43") (pinfunction "PA10_43") (pintype "bidirectional"))
    )
    (net (code "82") (name "unconnected-(MICROCONTROLLER-PA15-Pad50)") (class "Default")
      (node (ref "MICROCONTROLLER") (pin "50") (pinfunction "PA15_50") (pintype "bidirectional"))
    )
    (net (code "83") (name "unconnected-(MICROCONTROLLER-PB0-Pad26)") (class "Default")
      (node (ref "MICROCONTROLLER") (pin "26") (pinfunction "PB0_26") (pintype "bidirectional"))
    )
    (net (code "84") (name "unconnected-(MICROCONTROLLER-PB1-Pad27)") (class "Default")
      (node (ref "MICROCONTROLLER") (pin "27") (pinfunction "PB1_27") (pintype "bidirectional"))
    )
    (net (code "85") (name "unconnected-(MICROCONTROLLER-PB4-Pad56)") (class "Default")
      (node (ref "MICROCONTROLLER") (pin "56") (pinfunction "PB4_56") (pintype "bidirectional"))
    )
    (net (code "86") (name "unconnected-(MICROCONTROLLER-PB5-Pad57)") (class "Default")
      (node (ref "MICROCONTROLLER") (pin "57") (pinfunction "PB5_57") (pintype "bidirectional"))
    )
    (net (code "87") (name "unconnected-(MICROCONTROLLER-PB12-Pad33)") (class "Default")
      (node (ref "MICROCONTROLLER") (pin "33") (pinfunction "PB12_33") (pintype "bidirectional"))
    )
    (net (code "88") (name "unconnected-(MICROCONTROLLER-PC2-Pad10)") (class "Default")
      (node (ref "MICROCONTROLLER") (pin "10") (pinfunction "PC2_10") (pintype "bidirectional"))
    )
    (net (code "89") (name "unconnected-(MICROCONTROLLER-PC4-Pad24)") (class "Default")
      (node (ref "MICROCONTROLLER") (pin "24") (pinfunction "PC4_24") (pintype "bidirectional"))
    )
    (net (code "90") (name "unconnected-(MICROCONTROLLER-PC5-Pad25)") (class "Default")
      (node (ref "MICROCONTROLLER") (pin "25") (pinfunction "PC5_25") (pintype "bidirectional"))
    )
    (net (code "91") (name "unconnected-(MICROCONTROLLER-PC6-Pad37)") (class "Default")
      (node (ref "MICROCONTROLLER") (pin "37") (pinfunction "PC6_37") (pintype "bidirectional"))
    )
    (net (code "92") (name "unconnected-(MICROCONTROLLER-PC7-Pad38)") (class "Default")
      (node (ref "MICROCONTROLLER") (pin "38") (pinfunction "PC7_38") (pintype "bidirectional"))
    )
    (net (code "93") (name "unconnected-(MICROCONTROLLER-PC12-Pad53)") (class "Default")
      (node (ref "MICROCONTROLLER") (pin "53") (pinfunction "PC12_53") (pintype "bidirectional"))
    )
    (net (code "94") (name "unconnected-(MICROCONTROLLER-PC13-Pad2)") (class "Default")
      (node (ref "MICROCONTROLLER") (pin "2") (pinfunction "PC13_2") (pintype "bidirectional"))
    )
    (net (code "95") (name "unconnected-(MICROCONTROLLER-PC14-OSC32_IN-Pad3)") (class "Default")
      (node (ref "MICROCONTROLLER") (pin "3") (pinfunction "PC14-OSC32_IN_3") (pintype "bidirectional"))
    )
    (net (code "96") (name "unconnected-(MICROCONTROLLER-PC15-OSC32_OUT-Pad4)") (class "Default")
      (node (ref "MICROCONTROLLER") (pin "4") (pinfunction "PC15-OSC32_OUT_4") (pintype "bidirectional"))
    )
    (net (code "97") (name "unconnected-(MICROCONTROLLER-PD2-Pad54)") (class "Default")
      (node (ref "MICROCONTROLLER") (pin "54") (pinfunction "PD2_54") (pintype "bidirectional"))
    )
    (net (code "98") (name "unconnected-(MICROCONTROLLER-PH1-OSC_OUT-Pad6)") (class "Default")
      (node (ref "MICROCONTROLLER") (pin "6") (pinfunction "PH1-OSC_OUT_6") (pintype "bidirectional"))
    )
    (net (code "99") (name "unconnected-(USB_COMM_MODE_FILTER-ID-Pad4)") (class "Default")
      (node (ref "USB_COMM_MODE_FILTER") (pin "4") (pinfunction "ID_4") (pintype "passive"))
    )
    (net (code "100") (name "unconnected-(Y1-TRI-STATE-Pad1)") (class "Default")
      (node (ref "Y1") (pin "1") (pinfunction "TRI-STATE_1") (pintype "bidirectional"))
    )
  )
)
